# E-bookReaderSch.net
KiCad netlist of a schematic drawn in EAGLE
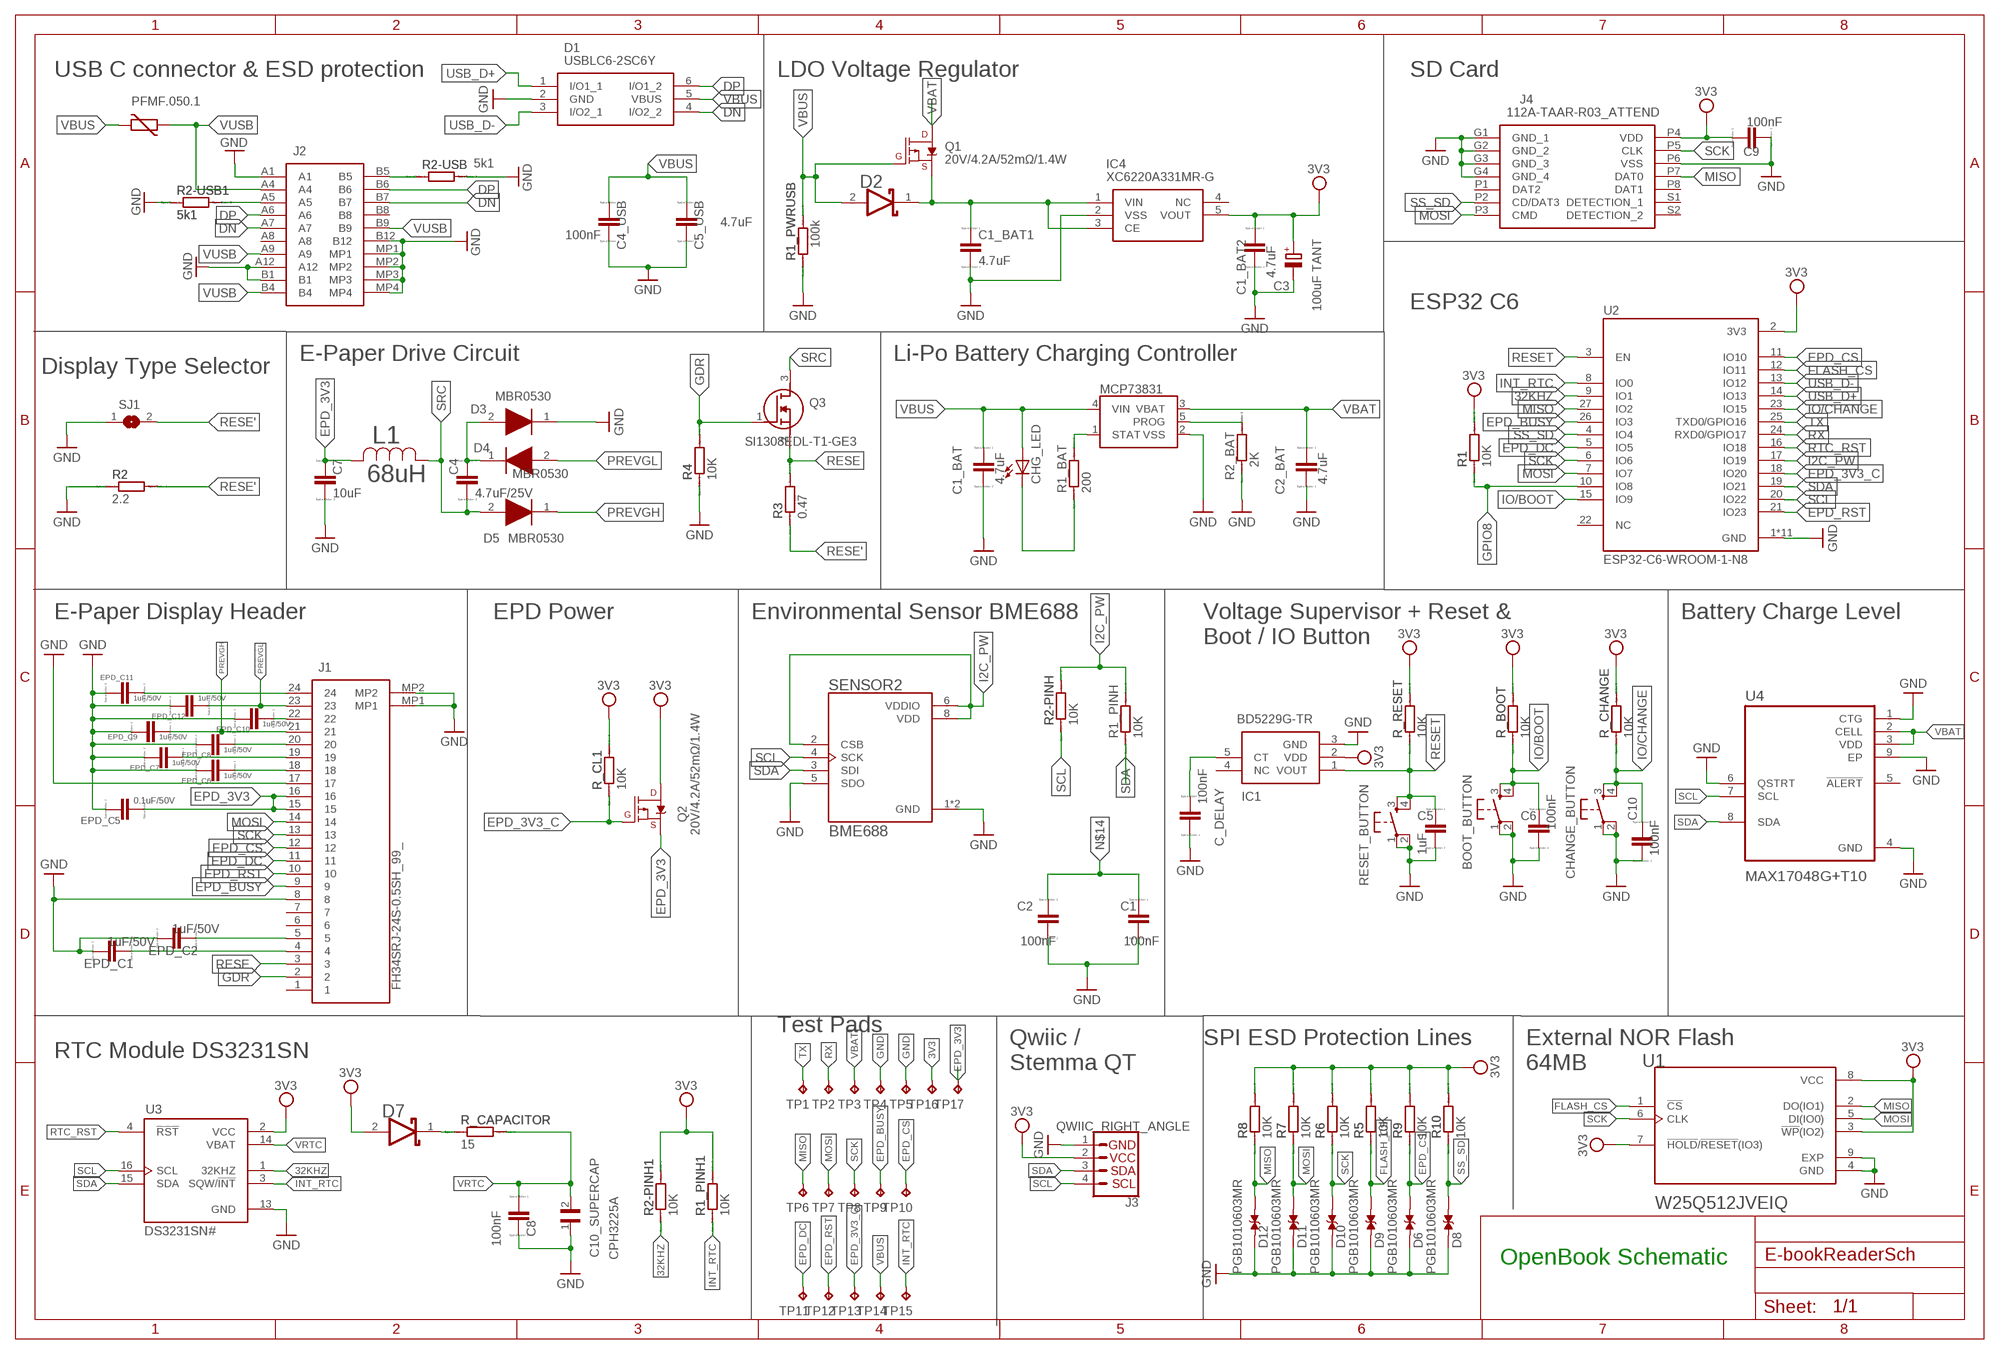
[diagram p0: schematic, sheet 1]

(export (version "E")
  (design (tool "Eeschema 10.0.6"))
  (components
    (comp (ref "BOOT_BUTTON")
      (value "BOOT_BUTTON")
      (footprint "eagle-import:MYBUTTON")
      (libsource (lib "eagle-import") (part "BUTTON_CUSYOMV1"))
    )
    (comp (ref "C1")
      (value "100nF")
      (footprint "eagle-import:EAGLE-LTSPICE_C0402")
      (libsource (lib "eagle-import") (part "EAGLE-LTSPICE_CC0402"))
    )
    (comp (ref "C1_BAT")
      (value "4.7uF")
      (footprint "eagle-import:EAGLE-LTSPICE_C0402")
      (libsource (lib "eagle-import") (part "EAGLE-LTSPICE_CC0402"))
    )
    (comp (ref "C1_BAT1")
      (value "4.7uF")
      (footprint "eagle-import:EAGLE-LTSPICE_C0402")
      (libsource (lib "eagle-import") (part "EAGLE-LTSPICE_CC0402"))
    )
    (comp (ref "C1_BAT2")
      (value "4.7uF")
      (footprint "eagle-import:EAGLE-LTSPICE_C0402")
      (libsource (lib "eagle-import") (part "EAGLE-LTSPICE_CC0402"))
    )
    (comp (ref "C2")
      (value "100nF")
      (footprint "eagle-import:EAGLE-LTSPICE_C0402")
      (libsource (lib "eagle-import") (part "EAGLE-LTSPICE_CC0402"))
    )
    (comp (ref "C2_BAT")
      (value "4.7uF")
      (footprint "eagle-import:EAGLE-LTSPICE_C0402")
      (libsource (lib "eagle-import") (part "EAGLE-LTSPICE_CC0402"))
    )
    (comp (ref "C3")
      (value "100uF TANT")
      (footprint "eagle-import:RCL_CT3528")
      (libsource (lib "eagle-import") (part "RCL_CPOL-EUCT3528"))
    )
    (comp (ref "C4")
      (value "4.7uF/25V")
      (footprint "eagle-import:ESP32_WROVER_EAGLE-LTSPICE_C0402")
      (libsource (lib "eagle-import") (part "ESP32_WROVER_EAGLE-LTSPICE_CC0402"))
    )
    (comp (ref "C4_USB")
      (value "100nF")
      (footprint "eagle-import:ESP32_WROVER_EAGLE-LTSPICE_C0402")
      (libsource (lib "eagle-import") (part "ESP32_WROVER_EAGLE-LTSPICE_CC0402"))
    )
    (comp (ref "C5")
      (value "1uF")
      (footprint "eagle-import:EAGLE-LTSPICE_C0402")
      (libsource (lib "eagle-import") (part "EAGLE-LTSPICE_CC0402"))
    )
    (comp (ref "C5_USB")
      (value "4.7uF")
      (footprint "eagle-import:EAGLE-LTSPICE_C0402")
      (libsource (lib "eagle-import") (part "EAGLE-LTSPICE_CC0402"))
    )
    (comp (ref "C6")
      (value "100nF")
      (footprint "eagle-import:EAGLE-LTSPICE_C0402")
      (libsource (lib "eagle-import") (part "EAGLE-LTSPICE_CC0402"))
    )
    (comp (ref "C7")
      (value "10uF")
      (footprint "eagle-import:ESP32_WROVER_EAGLE-LTSPICE_C0402")
      (libsource (lib "eagle-import") (part "ESP32_WROVER_EAGLE-LTSPICE_CC0402"))
    )
    (comp (ref "C8")
      (value "100nF")
      (footprint "eagle-import:ESP32_WROVER_EAGLE-LTSPICE_C0402")
      (libsource (lib "eagle-import") (part "ESP32_WROVER_EAGLE-LTSPICE_CC0402"))
    )
    (comp (ref "C9")
      (value "100nF")
      (footprint "eagle-import:EAGLE-LTSPICE_C0402")
      (libsource (lib "eagle-import") (part "EAGLE-LTSPICE_CC0402"))
    )
    (comp (ref "C10")
      (value "100nF")
      (footprint "eagle-import:EAGLE-LTSPICE_C0402")
      (libsource (lib "eagle-import") (part "EAGLE-LTSPICE_CC0402"))
    )
    (comp (ref "C10_SUPERCAP")
      (value "CPH3225A")
      (footprint "eagle-import:CAPCP3225X100N")
      (fields (field (name "MF") "Seiko Instruments"))
      (libsource (lib "eagle-import") (part "CPH3225A"))
    )
    (comp (ref "CHANGE_BUTTON")
      (value "CHANGE_BUTTON")
      (footprint "eagle-import:MYBUTTON")
      (libsource (lib "eagle-import") (part "BUTTON_CUSYOMV1"))
    )
    (comp (ref "CHG_LED")
      (value "ADAFRUIT_LEDCHIP-LED0603")
      (footprint "eagle-import:ADAFRUIT_CHIP-LED0603")
      (libsource (lib "eagle-import") (part "ADAFRUIT_LEDCHIP-LED0603"))
    )
    (comp (ref "C_DELAY")
      (value "100nF")
      (footprint "eagle-import:EAGLE-LTSPICE_C0402")
      (libsource (lib "eagle-import") (part "EAGLE-LTSPICE_CC0402"))
    )
    (comp (ref "D1")
      (value "USBLC6-2SC6Y")
      (footprint "eagle-import:SOT95P280X145-6N")
      (fields (field (name "MF") "STMicroelectronics"))
      (libsource (lib "eagle-import") (part "USBLC6-2SC6Y"))
    )
    (comp (ref "D2")
      (value "ESP32_WROVER_AVX---SD0805S020S1R0_AVX_SD0805S020S1R0_0_0AVX_SD0805S020S1R0_0_0")
      (footprint "eagle-import:ESP32_WROVER_AVX---SD0805S020S1R0_AVX_SD0805S020S1R0_0")
      (fields
        (field (name "DIGIKEY_PART_NUMBER") "478-7800-1-ND")
        (field (name "MF") "AVX")
        (field (name "MOUSER_PART_NUMBER") "581-SD0805S020S1R0")
      )
      (libsource (lib "eagle-import") (part "ESP32_WROVER_AVX---SD0805S020S1R0_AVX_SD0805S020S1R0_0_0AVX_SD0805S020S1R0_0_0"))
    )
    (comp (ref "D3")
      (value "MBR0530")
      (footprint "eagle-import:SOD3716X135N")
      (fields (field (name "MF") "ON Semiconductor"))
      (libsource (lib "eagle-import") (part "MBR0530"))
    )
    (comp (ref "D4")
      (value "MBR0530")
      (footprint "eagle-import:SOD3716X135N")
      (fields (field (name "MF") "ON Semiconductor"))
      (libsource (lib "eagle-import") (part "MBR0530"))
    )
    (comp (ref "D5")
      (value "MBR0530")
      (footprint "eagle-import:SOD3716X135N")
      (fields (field (name "MF") "ON Semiconductor"))
      (libsource (lib "eagle-import") (part "MBR0530"))
    )
    (comp (ref "D6")
      (value "PGB1010603MR")
      (footprint "eagle-import:DIOC1608X36N")
      (fields (field (name "MF") "Littelfuse Inc."))
      (libsource (lib "eagle-import") (part "PGB1010603MR"))
    )
    (comp (ref "D7")
      (value "SD0805S020S1R0")
      (footprint "eagle-import:ESP32_WROVER_AVX---SD0805S020S1R0_AVX_SD0805S020S1R0_0")
      (fields
        (field (name "DIGIKEY_PART_NUMBER") "478-7800-1-ND")
        (field (name "MF") "AVX")
        (field (name "MOUSER_PART_NUMBER") "581-SD0805S020S1R0")
      )
      (libsource (lib "eagle-import") (part "ESP32_WROVER_AVX---SD0805S020S1R0_AVX_SD0805S020S1R0_0_0AVX_SD0805S020S1R0_0_0"))
    )
    (comp (ref "D8")
      (value "PGB1010603MR")
      (footprint "eagle-import:DIOC1608X36N")
      (fields (field (name "MF") "Littelfuse Inc."))
      (libsource (lib "eagle-import") (part "PGB1010603MR"))
    )
    (comp (ref "D9")
      (value "PGB1010603MR")
      (footprint "eagle-import:DIOC1608X36N")
      (fields (field (name "MF") "Littelfuse Inc."))
      (libsource (lib "eagle-import") (part "PGB1010603MR"))
    )
    (comp (ref "D10")
      (value "PGB1010603MR")
      (footprint "eagle-import:DIOC1608X36N")
      (fields (field (name "MF") "Littelfuse Inc."))
      (libsource (lib "eagle-import") (part "PGB1010603MR"))
    )
    (comp (ref "D11")
      (value "PGB1010603MR")
      (footprint "eagle-import:DIOC1608X36N")
      (fields (field (name "MF") "Littelfuse Inc."))
      (libsource (lib "eagle-import") (part "PGB1010603MR"))
    )
    (comp (ref "D12")
      (value "PGB1010603MR")
      (footprint "eagle-import:DIOC1608X36N")
      (fields (field (name "MF") "Littelfuse Inc."))
      (libsource (lib "eagle-import") (part "PGB1010603MR"))
    )
    (comp (ref "EPD_C1")
      (value "1uF/50V")
      (footprint "eagle-import:ESP32_WROVER_EAGLE-LTSPICE_C0402")
      (libsource (lib "eagle-import") (part "ESP32_WROVER_EAGLE-LTSPICE_CC0402"))
    )
    (comp (ref "EPD_C2")
      (value "1uF/50V")
      (footprint "eagle-import:ESP32_WROVER_EAGLE-LTSPICE_C0402")
      (libsource (lib "eagle-import") (part "ESP32_WROVER_EAGLE-LTSPICE_CC0402"))
    )
    (comp (ref "EPD_C5")
      (value "0.1uF/50V")
      (footprint "eagle-import:ESP32_WROVER_EAGLE-LTSPICE_C0402")
      (libsource (lib "eagle-import") (part "ESP32_WROVER_EAGLE-LTSPICE_CC0402"))
    )
    (comp (ref "EPD_C6")
      (value "1uF/50V")
      (footprint "eagle-import:ESP32_WROVER_EAGLE-LTSPICE_C0402")
      (libsource (lib "eagle-import") (part "ESP32_WROVER_EAGLE-LTSPICE_CC0402"))
    )
    (comp (ref "EPD_C7")
      (value "1uF/50V")
      (footprint "eagle-import:ESP32_WROVER_EAGLE-LTSPICE_C0402")
      (libsource (lib "eagle-import") (part "ESP32_WROVER_EAGLE-LTSPICE_CC0402"))
    )
    (comp (ref "EPD_C8")
      (value "1uF/50V")
      (footprint "eagle-import:ESP32_WROVER_EAGLE-LTSPICE_C0402")
      (libsource (lib "eagle-import") (part "ESP32_WROVER_EAGLE-LTSPICE_CC0402"))
    )
    (comp (ref "EPD_C9")
      (value "1uF/50V")
      (footprint "eagle-import:ESP32_WROVER_EAGLE-LTSPICE_C0402")
      (libsource (lib "eagle-import") (part "ESP32_WROVER_EAGLE-LTSPICE_CC0402"))
    )
    (comp (ref "EPD_C10")
      (value "1uF/50V")
      (footprint "eagle-import:ESP32_WROVER_EAGLE-LTSPICE_C0402")
      (libsource (lib "eagle-import") (part "ESP32_WROVER_EAGLE-LTSPICE_CC0402"))
    )
    (comp (ref "EPD_C11")
      (value "1uF/50V")
      (footprint "eagle-import:ESP32_WROVER_EAGLE-LTSPICE_C0402")
      (libsource (lib "eagle-import") (part "ESP32_WROVER_EAGLE-LTSPICE_CC0402"))
    )
    (comp (ref "EPD_C12")
      (value "1uF/50V")
      (footprint "eagle-import:ESP32_WROVER_EAGLE-LTSPICE_C0402")
      (libsource (lib "eagle-import") (part "ESP32_WROVER_EAGLE-LTSPICE_CC0402"))
    )
    (comp (ref "IC1")
      (value "BD5229G-TR")
      (footprint "eagle-import:SOT95P280X125-5N")
      (fields (field (name "MOUSER_PART_NUMBER") "755-BD5229G-TR"))
      (libsource (lib "eagle-import") (part "BD5229G-TR"))
    )
    (comp (ref "IC4")
      (value "XC6220A331MR-G")
      (footprint "eagle-import:SOT95P280X120-5N")
      (fields (field (name "MOUSER_PART_NUMBER") "865-XC6220A331MR-G"))
      (libsource (lib "eagle-import") (part "XC6220A331MR-G"))
    )
    (comp (ref "J1")
      (value "FH34SRJ-24S-0.5SH_99_")
      (footprint "eagle-import:FH34SRJ24S05SH99")
      (fields
        (field (name "MANUFACTURER_PART_NUMBER") "FH34SRJ-24S-0.5SH(99)")
        (field (name "MOUSER_PART_NUMBER") "798-FH34SRJ24S05SH99")
      )
      (libsource (lib "eagle-import") (part "FH34SRJ-24S-0.5SH_99_"))
    )
    (comp (ref "J2")
      (value "SAMACSYS_PARTS_USB4110-GF-A")
      (footprint "eagle-import:SAMACSYS_PARTS_USB4110GFA")
      (fields
        (field (name "MANUFACTURER_PART_NUMBER") "USB4110-GF-A")
        (field (name "MOUSER_PART_NUMBER") "640-USB4110-GF-A")
      )
      (libsource (lib "eagle-import") (part "SAMACSYS_PARTS_USB4110-GF-A"))
    )
    (comp (ref "J3")
      (value "QWIIC_RIGHT_ANGLE")
      (footprint "eagle-import:JST04_1MM_RA")
      (libsource (lib "eagle-import") (part "QWIIC_CONNECTORJS-1MM"))
    )
    (comp (ref "J4")
      (value "112A-TAAR-R03_ATTEND")
      (footprint "eagle-import:112ATAARR03ATTEND")
      (fields (field (name "MANUFACTURER_PART_NUMBER") "112A-TAAR-R03 ATTEND"))
      (libsource (lib "eagle-import") (part "112A-TAAR-R03_ATTEND"))
    )
    (comp (ref "L1")
      (value "68uH")
      (footprint "eagle-import:IND_4828-WE-TPC_WRE")
      (fields
        (field (name "MANUFACTURER_PART_NUMBER") "744043680")
        (field (name "COPYRIGHT") "Copyright (C) 2024 Ultra Librarian. All rights reserved.")
      )
      (libsource (lib "eagle-import") (part "744043680IND_4828-WE-TPC_WRE"))
    )
    (comp (ref "MCP73831")
      (value "ESP32_WROVER_SPARKFUN-IC-POWER_MCP73831")
      (footprint "eagle-import:ESP32_WROVER_SPARKFUN-IC-POWER_SOT23-5")
      (libsource (lib "eagle-import") (part "ESP32_WROVER_SPARKFUN-IC-POWER_MCP73831"))
    )
    (comp (ref "PFMF.050.1")
      (value "ESP32C6_VARISTORCN1812")
      (footprint "eagle-import:ESP32C6_VARISTOR_CT_CN1812")
      (libsource (lib "eagle-import") (part "ESP32C6_VARISTORCN1812"))
    )
    (comp (ref "Q1")
      (value "20V/4.2A/52mΩ/1.4W")
      (footprint "eagle-import:ESP32_WROVER_SPARKFUN-DISCRETESEMI_SOT23-3")
      (libsource (lib "eagle-import") (part "ESP32_WROVER_SPARKFUN-DISCRETESEMI_MOSFET_PCH-DMG2305UX-7"))
    )
    (comp (ref "Q2")
      (value "20V/4.2A/52mΩ/1.4W")
      (footprint "eagle-import:ESP32_WROVER_SPARKFUN-DISCRETESEMI_SOT23-3")
      (libsource (lib "eagle-import") (part "ESP32_WROVER_SPARKFUN-DISCRETESEMI_MOSFET_PCH-DMG2305UX-7"))
    )
    (comp (ref "Q3")
      (value "SI1308EDL-T1-GE3")
      (footprint "eagle-import:SOT65P210X110-3N")
      (fields (field (name "MF") "Vishay Siliconix"))
      (libsource (lib "eagle-import") (part "SI1308EDL-T1-GE3"))
    )
    (comp (ref "R1")
      (value "10K")
      (footprint "eagle-import:ESP32_WROVER_EAGLE-LTSPICE_R0402")
      (libsource (lib "eagle-import") (part "ESP32_WROVER_EAGLE-LTSPICE_RR0402"))
    )
    (comp (ref "R1_BAT")
      (value "200")
      (footprint "eagle-import:ESP32_WROVER_EAGLE-LTSPICE_R0402")
      (libsource (lib "eagle-import") (part "ESP32_WROVER_EAGLE-LTSPICE_RR0402"))
    )
    (comp (ref "R1_PINH")
      (value "10K")
      (footprint "eagle-import:ESP32_WROVER_EAGLE-LTSPICE_R0402")
      (libsource (lib "eagle-import") (part "ESP32_WROVER_EAGLE-LTSPICE_RR0402"))
    )
    (comp (ref "R1_PINH1")
      (value "10K")
      (footprint "eagle-import:ESP32_WROVER_EAGLE-LTSPICE_R0402")
      (libsource (lib "eagle-import") (part "ESP32_WROVER_EAGLE-LTSPICE_RR0402"))
    )
    (comp (ref "R1_PWRUSB")
      (value "100k")
      (footprint "eagle-import:ESP32_WROVER_EAGLE-LTSPICE_R0402")
      (libsource (lib "eagle-import") (part "ESP32_WROVER_EAGLE-LTSPICE_RR0402"))
    )
    (comp (ref "R2")
      (value "2.2")
      (footprint "eagle-import:ESP32_WROVER_EAGLE-LTSPICE_R0402")
      (libsource (lib "eagle-import") (part "ESP32_WROVER_EAGLE-LTSPICE_RR0402"))
    )
    (comp (ref "R2-PINH")
      (value "10K")
      (footprint "eagle-import:ESP32_WROVER_EAGLE-LTSPICE_R0402")
      (libsource (lib "eagle-import") (part "ESP32_WROVER_EAGLE-LTSPICE_RR0402"))
    )
    (comp (ref "R2-PINH1")
      (value "10K")
      (footprint "eagle-import:ESP32_WROVER_EAGLE-LTSPICE_R0402")
      (libsource (lib "eagle-import") (part "ESP32_WROVER_EAGLE-LTSPICE_RR0402"))
    )
    (comp (ref "R2-USB")
      (value "5k1")
      (footprint "eagle-import:ESP32_WROVER_EAGLE-LTSPICE_R0402")
      (libsource (lib "eagle-import") (part "ESP32_WROVER_EAGLE-LTSPICE_RR0402"))
    )
    (comp (ref "R2-USB1")
      (value "5k1")
      (footprint "eagle-import:ESP32_WROVER_EAGLE-LTSPICE_R0402")
      (libsource (lib "eagle-import") (part "ESP32_WROVER_EAGLE-LTSPICE_RR0402"))
    )
    (comp (ref "R2_BAT")
      (value "2K")
      (footprint "eagle-import:ESP32_WROVER_EAGLE-LTSPICE_R0402")
      (libsource (lib "eagle-import") (part "ESP32_WROVER_EAGLE-LTSPICE_RR0402"))
    )
    (comp (ref "R3")
      (value "0.47")
      (footprint "eagle-import:ESP32_WROVER_EAGLE-LTSPICE_R0402")
      (libsource (lib "eagle-import") (part "ESP32_WROVER_EAGLE-LTSPICE_RR0402"))
    )
    (comp (ref "R4")
      (value "10K")
      (footprint "eagle-import:ESP32_WROVER_EAGLE-LTSPICE_R0402")
      (libsource (lib "eagle-import") (part "ESP32_WROVER_EAGLE-LTSPICE_RR0402"))
    )
    (comp (ref "R5")
      (value "10K")
      (footprint "eagle-import:ESP32_WROVER_EAGLE-LTSPICE_R0402")
      (libsource (lib "eagle-import") (part "ESP32_WROVER_EAGLE-LTSPICE_RR0402"))
    )
    (comp (ref "R6")
      (value "10K")
      (footprint "eagle-import:ESP32_WROVER_EAGLE-LTSPICE_R0402")
      (libsource (lib "eagle-import") (part "ESP32_WROVER_EAGLE-LTSPICE_RR0402"))
    )
    (comp (ref "R7")
      (value "10K")
      (footprint "eagle-import:ESP32_WROVER_EAGLE-LTSPICE_R0402")
      (libsource (lib "eagle-import") (part "ESP32_WROVER_EAGLE-LTSPICE_RR0402"))
    )
    (comp (ref "R8")
      (value "10K")
      (footprint "eagle-import:ESP32_WROVER_EAGLE-LTSPICE_R0402")
      (libsource (lib "eagle-import") (part "ESP32_WROVER_EAGLE-LTSPICE_RR0402"))
    )
    (comp (ref "R9")
      (value "10K")
      (footprint "eagle-import:ESP32_WROVER_EAGLE-LTSPICE_R0402")
      (libsource (lib "eagle-import") (part "ESP32_WROVER_EAGLE-LTSPICE_RR0402"))
    )
    (comp (ref "R10")
      (value "10K")
      (footprint "eagle-import:ESP32_WROVER_EAGLE-LTSPICE_R0402")
      (libsource (lib "eagle-import") (part "ESP32_WROVER_EAGLE-LTSPICE_RR0402"))
    )
    (comp (ref "RESET_BUTTON")
      (value "RESET_BUTTON")
      (footprint "eagle-import:MYBUTTON")
      (libsource (lib "eagle-import") (part "BUTTON_CUSYOMV1"))
    )
    (comp (ref "R_BOOT")
      (value "10K")
      (footprint "eagle-import:ESP32_WROVER_EAGLE-LTSPICE_R0402")
      (libsource (lib "eagle-import") (part "ESP32_WROVER_EAGLE-LTSPICE_RR0402"))
    )
    (comp (ref "R_CAPACITOR")
      (value "15")
      (footprint "eagle-import:ESP32_WROVER_EAGLE-LTSPICE_R0402")
      (libsource (lib "eagle-import") (part "ESP32_WROVER_EAGLE-LTSPICE_RR0402"))
    )
    (comp (ref "R_CHANGE")
      (value "10K")
      (footprint "eagle-import:ESP32_WROVER_EAGLE-LTSPICE_R0402")
      (libsource (lib "eagle-import") (part "ESP32_WROVER_EAGLE-LTSPICE_RR0402"))
    )
    (comp (ref "R_CL1")
      (value "10K")
      (footprint "eagle-import:ESP32_WROVER_EAGLE-LTSPICE_R0402")
      (libsource (lib "eagle-import") (part "ESP32_WROVER_EAGLE-LTSPICE_RR0402"))
    )
    (comp (ref "R_RESET")
      (value "10K")
      (footprint "eagle-import:ESP32_WROVER_EAGLE-LTSPICE_R0402")
      (libsource (lib "eagle-import") (part "ESP32_WROVER_EAGLE-LTSPICE_RR0402"))
    )
    (comp (ref "SENSOR2")
      (value "BME688")
      (footprint "eagle-import:ESP32_WROVER_BME680_PSON80P300X300X100-8N")
      (fields (field (name "MF") "Bosch Sensortec") (field (name "MP") "BME680"))
      (libsource (lib "eagle-import") (part "ESP32_WROVER_BME680_BME680"))
    )
    (comp (ref "SJ1") (value "SJ") (footprint "eagle-import:SJ") (libsource (lib "eagle-import") (part "SJ")))
    (comp (ref "TP1")
      (value "TPTP20R")
      (footprint "eagle-import:TP20R")
      (libsource (lib "eagle-import") (part "TPTP20R"))
    )
    (comp (ref "TP2")
      (value "TPTP20R")
      (footprint "eagle-import:TP20R")
      (libsource (lib "eagle-import") (part "TPTP20R"))
    )
    (comp (ref "TP3")
      (value "TPTP20R")
      (footprint "eagle-import:TP20R")
      (libsource (lib "eagle-import") (part "TPTP20R"))
    )
    (comp (ref "TP4")
      (value "TPTP20R")
      (footprint "eagle-import:TP20R")
      (libsource (lib "eagle-import") (part "TPTP20R"))
    )
    (comp (ref "TP5")
      (value "TPTP20R")
      (footprint "eagle-import:TP20R")
      (libsource (lib "eagle-import") (part "TPTP20R"))
    )
    (comp (ref "TP6")
      (value "TPTP20R")
      (footprint "eagle-import:TP20R")
      (libsource (lib "eagle-import") (part "TPTP20R"))
    )
    (comp (ref "TP7")
      (value "TPTP20R")
      (footprint "eagle-import:TP20R")
      (libsource (lib "eagle-import") (part "TPTP20R"))
    )
    (comp (ref "TP8")
      (value "TPTP20R")
      (footprint "eagle-import:TP20R")
      (libsource (lib "eagle-import") (part "TPTP20R"))
    )
    (comp (ref "TP9")
      (value "TPTP20R")
      (footprint "eagle-import:TP20R")
      (libsource (lib "eagle-import") (part "TPTP20R"))
    )
    (comp (ref "TP10")
      (value "TPTP20R")
      (footprint "eagle-import:TP20R")
      (libsource (lib "eagle-import") (part "TPTP20R"))
    )
    (comp (ref "TP11")
      (value "TPTP20R")
      (footprint "eagle-import:TP20R")
      (libsource (lib "eagle-import") (part "TPTP20R"))
    )
    (comp (ref "TP12")
      (value "TPTP20R")
      (footprint "eagle-import:TP20R")
      (libsource (lib "eagle-import") (part "TPTP20R"))
    )
    (comp (ref "TP13")
      (value "TPTP20R")
      (footprint "eagle-import:TP20R")
      (libsource (lib "eagle-import") (part "TPTP20R"))
    )
    (comp (ref "TP14")
      (value "TPTP20R")
      (footprint "eagle-import:TP20R")
      (libsource (lib "eagle-import") (part "TPTP20R"))
    )
    (comp (ref "TP15")
      (value "TPTP20R")
      (footprint "eagle-import:TP20R")
      (libsource (lib "eagle-import") (part "TPTP20R"))
    )
    (comp (ref "TP16")
      (value "TPTP20R")
      (footprint "eagle-import:TP20R")
      (libsource (lib "eagle-import") (part "TPTP20R"))
    )
    (comp (ref "TP17")
      (value "TPTP20R")
      (footprint "eagle-import:TP20R")
      (libsource (lib "eagle-import") (part "TPTP20R"))
    )
    (comp (ref "U1")
      (value "W25Q512JVEIQ")
      (footprint "eagle-import:SON127P600X800X80-9N")
      (fields (field (name "MF") "Winbond Electronics"))
      (libsource (lib "eagle-import") (part "W25Q512JVEIQ"))
    )
    (comp (ref "U2")
      (value "ESP32-C6-WROOM-1-N8")
      (footprint "eagle-import:XCVR_ESP32-C6-WROOM-1-N8")
      (fields (field (name "MF") "Espressif Systems"))
      (libsource (lib "eagle-import") (part "ESP32-C6-WROOM-1-N8"))
    )
    (comp (ref "U3")
      (value "DS3231SN#")
      (footprint "eagle-import:SOIC127P1032X265-16N")
      (fields (field (name "MF") "Analog Devices"))
      (libsource (lib "eagle-import") (part "DS3231SN#"))
    )
    (comp (ref "U4")
      (value "MAX17048G+T10")
      (footprint "eagle-import:SON50P200X200X80-9N")
      (fields (field (name "MF") "Analog Devices"))
      (libsource (lib "eagle-import") (part "MAX17048G+T10"))
    )
  )
  (nets
    (net (code "1") (name "3V3") (class "Default")
      (node (ref "C1_BAT2") (pin "1") (pinfunction "1_1") (pintype "passive"))
      (node (ref "C3") (pin "+") (pinfunction "+_+") (pintype "passive"))
      (node (ref "C9") (pin "1") (pinfunction "1_1") (pintype "passive"))
      (node (ref "D7") (pin "2") (pinfunction "ANODE_2") (pintype "bidirectional"))
      (node (ref "IC1") (pin "2") (pinfunction "VDD_2") (pintype "bidirectional"))
      (node (ref "IC4") (pin "5") (pinfunction "VOUT_5") (pintype "bidirectional"))
      (node (ref "J3") (pin "2") (pinfunction "2_2") (pintype "power_in"))
      (node (ref "J4") (pin "P4") (pinfunction "VDD_P4") (pintype "bidirectional"))
      (node (ref "Q2") (pin "3") (pinfunction "D_3") (pintype "bidirectional"))
      (node (ref "R1") (pin "2") (pinfunction "2_2") (pintype "passive"))
      (node (ref "R10") (pin "2") (pinfunction "2_2") (pintype "passive"))
      (node (ref "R1_PINH1") (pin "2") (pinfunction "2_2") (pintype "passive"))
      (node (ref "R2-PINH1") (pin "2") (pinfunction "2_2") (pintype "passive"))
      (node (ref "R5") (pin "2") (pinfunction "2_2") (pintype "passive"))
      (node (ref "R6") (pin "2") (pinfunction "2_2") (pintype "passive"))
      (node (ref "R7") (pin "2") (pinfunction "2_2") (pintype "passive"))
      (node (ref "R8") (pin "2") (pinfunction "2_2") (pintype "passive"))
      (node (ref "R9") (pin "2") (pinfunction "2_2") (pintype "passive"))
      (node (ref "R_BOOT") (pin "2") (pinfunction "2_2") (pintype "passive"))
      (node (ref "R_CHANGE") (pin "2") (pinfunction "2_2") (pintype "passive"))
      (node (ref "R_CL1") (pin "2") (pinfunction "2_2") (pintype "passive"))
      (node (ref "R_RESET") (pin "2") (pinfunction "2_2") (pintype "passive"))
      (node (ref "TP16") (pin "TP") (pinfunction "TP_TP") (pintype "input"))
      (node (ref "U1") (pin "3") (pinfunction "~{WP}(IO2)_3") (pintype "bidirectional"))
      (node (ref "U1") (pin "7") (pinfunction "~{HOLD}/~{RESET}(IO3)_7") (pintype "bidirectional"))
      (node (ref "U1") (pin "8") (pinfunction "VCC_8") (pintype "power_in"))
      (node (ref "U2") (pin "2") (pinfunction "3V3_2") (pintype "power_in"))
      (node (ref "U3") (pin "2") (pinfunction "VCC_2") (pintype "power_in"))
    )
    (net (code "2") (name "32KHZ") (class "Default")
      (node (ref "R2-PINH1") (pin "1") (pinfunction "1_1") (pintype "passive"))
      (node (ref "U2") (pin "9") (pinfunction "IO1_9") (pintype "bidirectional"))
      (node (ref "U3") (pin "1") (pinfunction "32KHZ_1") (pintype "output"))
    )
    (net (code "3") (name "DN") (class "Default")
      (node (ref "D1") (pin "4") (pinfunction "I/O2_2_4") (pintype "bidirectional"))
      (node (ref "J2") (pin "A7") (pinfunction "A7_A7") (pintype "bidirectional"))
      (node (ref "J2") (pin "B7") (pinfunction "B7_B7") (pintype "bidirectional"))
    )
    (net (code "4") (name "DP") (class "Default")
      (node (ref "D1") (pin "6") (pinfunction "I/O1_2_6") (pintype "bidirectional"))
      (node (ref "J2") (pin "A6") (pinfunction "A6_A6") (pintype "bidirectional"))
      (node (ref "J2") (pin "B6") (pinfunction "B6_B6") (pintype "bidirectional"))
    )
    (net (code "5") (name "EPD_3V3") (class "Default")
      (node (ref "C7") (pin "1") (pinfunction "1_1") (pintype "passive"))
      (node (ref "EPD_C5") (pin "1") (pinfunction "1_1") (pintype "passive"))
      (node (ref "J1") (pin "15") (pinfunction "15_15") (pintype "bidirectional"))
      (node (ref "J1") (pin "16") (pinfunction "16_16") (pintype "bidirectional"))
      (node (ref "L1") (pin "2") (pinfunction "2_2") (pintype "passive"))
      (node (ref "Q2") (pin "2") (pinfunction "S_2") (pintype "bidirectional"))
      (node (ref "TP17") (pin "TP") (pinfunction "TP_TP") (pintype "input"))
    )
    (net (code "6") (name "EPD_3V3_C") (class "Default")
      (node (ref "Q2") (pin "1") (pinfunction "G_1") (pintype "bidirectional"))
      (node (ref "R_CL1") (pin "1") (pinfunction "1_1") (pintype "passive"))
      (node (ref "TP13") (pin "TP") (pinfunction "TP_TP") (pintype "input"))
      (node (ref "U2") (pin "18") (pinfunction "IO20_18") (pintype "bidirectional"))
    )
    (net (code "7") (name "EPD_BUSY") (class "Default")
      (node (ref "J1") (pin "9") (pinfunction "9_9") (pintype "bidirectional"))
      (node (ref "TP9") (pin "TP") (pinfunction "TP_TP") (pintype "input"))
      (node (ref "U2") (pin "26") (pinfunction "IO3_26") (pintype "bidirectional"))
    )
    (net (code "8") (name "EPD_CS") (class "Default")
      (node (ref "D6") (pin "2") (pinfunction "2_2") (pintype "passive"))
      (node (ref "J1") (pin "12") (pinfunction "12_12") (pintype "bidirectional"))
      (node (ref "R9") (pin "1") (pinfunction "1_1") (pintype "passive"))
      (node (ref "TP10") (pin "TP") (pinfunction "TP_TP") (pintype "input"))
      (node (ref "U2") (pin "11") (pinfunction "IO10_11") (pintype "bidirectional"))
    )
    (net (code "9") (name "EPD_DC") (class "Default")
      (node (ref "J1") (pin "11") (pinfunction "11_11") (pintype "bidirectional"))
      (node (ref "TP11") (pin "TP") (pinfunction "TP_TP") (pintype "input"))
      (node (ref "U2") (pin "5") (pinfunction "IO5_5") (pintype "bidirectional"))
    )
    (net (code "10") (name "EPD_RST") (class "Default")
      (node (ref "J1") (pin "10") (pinfunction "10_10") (pintype "bidirectional"))
      (node (ref "TP12") (pin "TP") (pinfunction "TP_TP") (pintype "input"))
      (node (ref "U2") (pin "21") (pinfunction "IO23_21") (pintype "bidirectional"))
    )
    (net (code "11") (name "FLASH_CS") (class "Default")
      (node (ref "D9") (pin "2") (pinfunction "2_2") (pintype "passive"))
      (node (ref "R5") (pin "1") (pinfunction "1_1") (pintype "passive"))
      (node (ref "U1") (pin "1") (pinfunction "~{CS}_1") (pintype "input"))
      (node (ref "U2") (pin "12") (pinfunction "IO11_12") (pintype "bidirectional"))
    )
    (net (code "12") (name "GDR") (class "Default")
      (node (ref "J1") (pin "2") (pinfunction "2_2") (pintype "bidirectional"))
      (node (ref "Q3") (pin "1") (pinfunction "G_1") (pintype "bidirectional"))
      (node (ref "R4") (pin "2") (pinfunction "2_2") (pintype "passive"))
    )
    (net (code "13") (name "GND") (class "Default")
      (node (ref "BOOT_BUTTON") (pin "1") (pinfunction "1_1") (pintype "passive"))
      (node (ref "BOOT_BUTTON") (pin "2") (pinfunction "2_2") (pintype "passive"))
      (node (ref "C1") (pin "2") (pinfunction "2_2") (pintype "passive"))
      (node (ref "C10") (pin "2") (pinfunction "2_2") (pintype "passive"))
      (node (ref "C10_SUPERCAP") (pin "1") (pinfunction "1_1") (pintype "passive"))
      (node (ref "C1_BAT") (pin "2") (pinfunction "2_2") (pintype "passive"))
      (node (ref "C1_BAT1") (pin "2") (pinfunction "2_2") (pintype "passive"))
      (node (ref "C1_BAT2") (pin "2") (pinfunction "2_2") (pintype "passive"))
      (node (ref "C2") (pin "2") (pinfunction "2_2") (pintype "passive"))
      (node (ref "C2_BAT") (pin "2") (pinfunction "2_2") (pintype "passive"))
      (node (ref "C3") (pin "-") (pinfunction "-_-") (pintype "passive"))
      (node (ref "C4_USB") (pin "2") (pinfunction "2_2") (pintype "passive"))
      (node (ref "C5") (pin "2") (pinfunction "2_2") (pintype "passive"))
      (node (ref "C5_USB") (pin "2") (pinfunction "2_2") (pintype "passive"))
      (node (ref "C6") (pin "2") (pinfunction "2_2") (pintype "passive"))
      (node (ref "C7") (pin "2") (pinfunction "2_2") (pintype "passive"))
      (node (ref "C8") (pin "2") (pinfunction "2_2") (pintype "passive"))
      (node (ref "C9") (pin "2") (pinfunction "2_2") (pintype "passive"))
      (node (ref "CHANGE_BUTTON") (pin "1") (pinfunction "1_1") (pintype "passive"))
      (node (ref "CHANGE_BUTTON") (pin "2") (pinfunction "2_2") (pintype "passive"))
      (node (ref "C_DELAY") (pin "2") (pinfunction "2_2") (pintype "passive"))
      (node (ref "D1") (pin "2") (pinfunction "GND_2") (pintype "bidirectional"))
      (node (ref "D10") (pin "1") (pinfunction "1_1") (pintype "passive"))
      (node (ref "D11") (pin "1") (pinfunction "1_1") (pintype "passive"))
      (node (ref "D12") (pin "1") (pinfunction "1_1") (pintype "passive"))
      (node (ref "D3") (pin "1") (pinfunction "K_1") (pintype "bidirectional"))
      (node (ref "D6") (pin "1") (pinfunction "1_1") (pintype "passive"))
      (node (ref "D8") (pin "1") (pinfunction "1_1") (pintype "passive"))
      (node (ref "D9") (pin "1") (pinfunction "1_1") (pintype "passive"))
      (node (ref "EPD_C1") (pin "2") (pinfunction "2_2") (pintype "passive"))
      (node (ref "EPD_C10") (pin "2") (pinfunction "2_2") (pintype "passive"))
      (node (ref "EPD_C11") (pin "2") (pinfunction "2_2") (pintype "passive"))
      (node (ref "EPD_C12") (pin "2") (pinfunction "2_2") (pintype "passive"))
      (node (ref "EPD_C2") (pin "2") (pinfunction "2_2") (pintype "passive"))
      (node (ref "EPD_C5") (pin "2") (pinfunction "2_2") (pintype "passive"))
      (node (ref "EPD_C6") (pin "2") (pinfunction "2_2") (pintype "passive"))
      (node (ref "EPD_C7") (pin "2") (pinfunction "2_2") (pintype "passive"))
      (node (ref "EPD_C8") (pin "2") (pinfunction "2_2") (pintype "passive"))
      (node (ref "EPD_C9") (pin "2") (pinfunction "2_2") (pintype "passive"))
      (node (ref "IC1") (pin "3") (pinfunction "GND_3") (pintype "bidirectional"))
      (node (ref "IC4") (pin "2") (pinfunction "VSS_2") (pintype "bidirectional"))
      (node (ref "J1") (pin "17") (pinfunction "17_17") (pintype "bidirectional"))
      (node (ref "J1") (pin "8") (pinfunction "8_8") (pintype "bidirectional"))
      (node (ref "J1") (pin "MP1") (pinfunction "MP1_MP1") (pintype "bidirectional"))
      (node (ref "J1") (pin "MP2") (pinfunction "MP2_MP2") (pintype "bidirectional"))
      (node (ref "J2") (pin "A1") (pinfunction "A1_A1") (pintype "bidirectional"))
      (node (ref "J2") (pin "A12") (pinfunction "A12_A12") (pintype "bidirectional"))
      (node (ref "J2") (pin "B1") (pinfunction "B1_B1") (pintype "bidirectional"))
      (node (ref "J2") (pin "B12") (pinfunction "B12_B12") (pintype "bidirectional"))
      (node (ref "J2") (pin "MP1") (pinfunction "MP1_MP1") (pintype "bidirectional"))
      (node (ref "J2") (pin "MP2") (pinfunction "MP2_MP2") (pintype "bidirectional"))
      (node (ref "J2") (pin "MP3") (pinfunction "MP3_MP3") (pintype "bidirectional"))
      (node (ref "J2") (pin "MP4") (pinfunction "MP4_MP4") (pintype "bidirectional"))
      (node (ref "J3") (pin "1") (pinfunction "1_1") (pintype "power_in"))
      (node (ref "J4") (pin "G1") (pinfunction "GND_1_G1") (pintype "bidirectional"))
      (node (ref "J4") (pin "G2") (pinfunction "GND_2_G2") (pintype "bidirectional"))
      (node (ref "J4") (pin "G3") (pinfunction "GND_3_G3") (pintype "bidirectional"))
      (node (ref "J4") (pin "G4") (pinfunction "GND_4_G4") (pintype "bidirectional"))
      (node (ref "J4") (pin "P6") (pinfunction "VSS_P6") (pintype "bidirectional"))
      (node (ref "MCP73831") (pin "2") (pinfunction "VSS_2") (pintype "power_in"))
      (node (ref "R1_PWRUSB") (pin "1") (pinfunction "1_1") (pintype "passive"))
      (node (ref "R2") (pin "1") (pinfunction "1_1") (pintype "passive"))
      (node (ref "R2-USB") (pin "2") (pinfunction "2_2") (pintype "passive"))
      (node (ref "R2-USB1") (pin "1") (pinfunction "1_1") (pintype "passive"))
      (node (ref "R2_BAT") (pin "1") (pinfunction "1_1") (pintype "passive"))
      (node (ref "R4") (pin "1") (pinfunction "1_1") (pintype "passive"))
      (node (ref "RESET_BUTTON") (pin "1") (pinfunction "1_1") (pintype "passive"))
      (node (ref "RESET_BUTTON") (pin "2") (pinfunction "2_2") (pintype "passive"))
      (node (ref "SENSOR2") (pin "1") (pinfunction "GND_1") (pintype "power_in"))
      (node (ref "SENSOR2") (pin "5") (pinfunction "SDO_5") (pintype "bidirectional"))
      (node (ref "SENSOR2") (pin "7") (pinfunction "GND_7") (pintype "power_in"))
      (node (ref "SJ1") (pin "1") (pinfunction "1_1") (pintype "passive"))
      (node (ref "TP4") (pin "TP") (pinfunction "TP_TP") (pintype "input"))
      (node (ref "TP5") (pin "TP") (pinfunction "TP_TP") (pintype "input"))
      (node (ref "U1") (pin "4") (pinfunction "GND_4") (pintype "power_in"))
      (node (ref "U1") (pin "9") (pinfunction "EXP_9") (pintype "passive"))
      (node (ref "U2") (pin "1") (pinfunction "GND_1") (pintype "power_in"))
      (node (ref "U2") (pin "28") (pinfunction "GND_28") (pintype "power_in"))
      (node (ref "U2") (pin "29_1") (pinfunction "GND_29_1") (pintype "power_in"))
      (node (ref "U2") (pin "29_2") (pinfunction "GND_29_2") (pintype "power_in"))
      (node (ref "U2") (pin "29_3") (pinfunction "GND_29_3") (pintype "power_in"))
      (node (ref "U2") (pin "29_4") (pinfunction "GND_29_4") (pintype "power_in"))
      (node (ref "U2") (pin "29_5") (pinfunction "GND_29_5") (pintype "power_in"))
      (node (ref "U2") (pin "29_6") (pinfunction "GND_29_6") (pintype "power_in"))
      (node (ref "U2") (pin "29_7") (pinfunction "GND_29_7") (pintype "power_in"))
      (node (ref "U2") (pin "29_8") (pinfunction "GND_29_8") (pintype "power_in"))
      (node (ref "U2") (pin "29_9") (pinfunction "GND_29_9") (pintype "power_in"))
      (node (ref "U3") (pin "13") (pinfunction "GND_13") (pintype "power_in"))
      (node (ref "U4") (pin "1") (pinfunction "CTG_1") (pintype "power_in"))
      (node (ref "U4") (pin "4") (pinfunction "GND_4") (pintype "power_in"))
      (node (ref "U4") (pin "6") (pinfunction "QSTRT_6") (pintype "input"))
      (node (ref "U4") (pin "9") (pinfunction "EP_9") (pintype "power_in"))
    )
    (net (code "14") (name "GPIO8") (class "Default")
      (node (ref "R1") (pin "1") (pinfunction "1_1") (pintype "passive"))
      (node (ref "U2") (pin "10") (pinfunction "IO8_10") (pintype "bidirectional"))
    )
    (net (code "15") (name "I2C_PW") (class "Default")
      (node (ref "R1_PINH") (pin "2") (pinfunction "2_2") (pintype "passive"))
      (node (ref "R2-PINH") (pin "2") (pinfunction "2_2") (pintype "passive"))
      (node (ref "SENSOR2") (pin "2") (pinfunction "CSB_2") (pintype "input"))
      (node (ref "SENSOR2") (pin "6") (pinfunction "VDDIO_6") (pintype "power_in"))
      (node (ref "SENSOR2") (pin "8") (pinfunction "VDD_8") (pintype "power_in"))
      (node (ref "U2") (pin "17") (pinfunction "IO19_17") (pintype "bidirectional"))
    )
    (net (code "16") (name "INT_RTC") (class "Default")
      (node (ref "R1_PINH1") (pin "1") (pinfunction "1_1") (pintype "passive"))
      (node (ref "TP15") (pin "TP") (pinfunction "TP_TP") (pintype "input"))
      (node (ref "U2") (pin "8") (pinfunction "IO0_8") (pintype "bidirectional"))
      (node (ref "U3") (pin "3") (pinfunction "SQW/~{INT}_3") (pintype "output"))
    )
    (net (code "17") (name "IO{slash}BOOT") (class "Default")
      (node (ref "BOOT_BUTTON") (pin "3") (pinfunction "3_3") (pintype "passive"))
      (node (ref "BOOT_BUTTON") (pin "4") (pinfunction "4_4") (pintype "passive"))
      (node (ref "C6") (pin "1") (pinfunction "1_1") (pintype "passive"))
      (node (ref "R_BOOT") (pin "1") (pinfunction "1_1") (pintype "passive"))
      (node (ref "U2") (pin "15") (pinfunction "IO9_15") (pintype "bidirectional"))
    )
    (net (code "18") (name "IO{slash}CHANGE") (class "Default")
      (node (ref "C10") (pin "1") (pinfunction "1_1") (pintype "passive"))
      (node (ref "CHANGE_BUTTON") (pin "3") (pinfunction "3_3") (pintype "passive"))
      (node (ref "CHANGE_BUTTON") (pin "4") (pinfunction "4_4") (pintype "passive"))
      (node (ref "R_CHANGE") (pin "1") (pinfunction "1_1") (pintype "passive"))
      (node (ref "U2") (pin "23") (pinfunction "IO15_23") (pintype "bidirectional"))
    )
    (net (code "19") (name "MISO") (class "Default")
      (node (ref "D12") (pin "2") (pinfunction "2_2") (pintype "passive"))
      (node (ref "J4") (pin "P7") (pinfunction "DAT0_P7") (pintype "bidirectional"))
      (node (ref "R8") (pin "1") (pinfunction "1_1") (pintype "passive"))
      (node (ref "TP6") (pin "TP") (pinfunction "TP_TP") (pintype "input"))
      (node (ref "U1") (pin "2") (pinfunction "DO(IO1)_2") (pintype "bidirectional"))
      (node (ref "U2") (pin "27") (pinfunction "IO2_27") (pintype "bidirectional"))
    )
    (net (code "20") (name "MOSI") (class "Default")
      (node (ref "D11") (pin "2") (pinfunction "2_2") (pintype "passive"))
      (node (ref "J1") (pin "14") (pinfunction "14_14") (pintype "bidirectional"))
      (node (ref "J4") (pin "P3") (pinfunction "CMD_P3") (pintype "bidirectional"))
      (node (ref "R7") (pin "1") (pinfunction "1_1") (pintype "passive"))
      (node (ref "TP7") (pin "TP") (pinfunction "TP_TP") (pintype "input"))
      (node (ref "U1") (pin "5") (pinfunction "DI(IO0)_5") (pintype "bidirectional"))
      (node (ref "U2") (pin "7") (pinfunction "IO7_7") (pintype "bidirectional"))
    )
    (net (code "21") (name "N$14") (class "Default")
      (node (ref "C1") (pin "1") (pinfunction "1_1") (pintype "passive"))
      (node (ref "C2") (pin "1") (pinfunction "1_1") (pintype "passive"))
    )
    (net (code "22") (name "Net-(CHG_LED-PadC)") (class "Default")
      (node (ref "CHG_LED") (pin "C") (pinfunction "C_C") (pintype "passive"))
      (node (ref "R1_BAT") (pin "1") (pinfunction "1_1") (pintype "passive"))
    )
    (net (code "23") (name "Net-(D2-CATHODE)") (class "Default")
      (node (ref "C1_BAT1") (pin "1") (pinfunction "1_1") (pintype "passive"))
      (node (ref "D2") (pin "1") (pinfunction "CATHODE_1") (pintype "bidirectional"))
      (node (ref "IC4") (pin "1") (pinfunction "VIN_1") (pintype "bidirectional"))
      (node (ref "IC4") (pin "3") (pinfunction "CE_3") (pintype "bidirectional"))
      (node (ref "Q1") (pin "2") (pinfunction "S_2") (pintype "bidirectional"))
    )
    (net (code "24") (name "Net-(D3-A)") (class "Default")
      (node (ref "C4") (pin "1") (pinfunction "1_1") (pintype "passive"))
      (node (ref "D3") (pin "2") (pinfunction "A_2") (pintype "bidirectional"))
      (node (ref "D4") (pin "1") (pinfunction "K_1") (pintype "bidirectional"))
    )
    (net (code "25") (name "Net-(D7-CATHODE)") (class "Default")
      (node (ref "D7") (pin "1") (pinfunction "CATHODE_1") (pintype "bidirectional"))
      (node (ref "R_CAPACITOR") (pin "1") (pinfunction "1_1") (pintype "passive"))
    )
    (net (code "26") (name "Net-(EPD_C1-Pad1)") (class "Default")
      (node (ref "EPD_C1") (pin "1") (pinfunction "1_1") (pintype "passive"))
      (node (ref "J1") (pin "4") (pinfunction "4_4") (pintype "bidirectional"))
    )
    (net (code "27") (name "Net-(EPD_C2-Pad1)") (class "Default")
      (node (ref "EPD_C2") (pin "1") (pinfunction "1_1") (pintype "passive"))
      (node (ref "J1") (pin "5") (pinfunction "5_5") (pintype "bidirectional"))
    )
    (net (code "28") (name "Net-(EPD_C6-Pad1)") (class "Default")
      (node (ref "EPD_C6") (pin "1") (pinfunction "1_1") (pintype "passive"))
      (node (ref "J1") (pin "18") (pinfunction "18_18") (pintype "bidirectional"))
    )
    (net (code "29") (name "Net-(EPD_C7-Pad1)") (class "Default")
      (node (ref "EPD_C7") (pin "1") (pinfunction "1_1") (pintype "passive"))
      (node (ref "J1") (pin "19") (pinfunction "19_19") (pintype "bidirectional"))
    )
    (net (code "30") (name "Net-(EPD_C8-Pad1)") (class "Default")
      (node (ref "EPD_C8") (pin "1") (pinfunction "1_1") (pintype "passive"))
      (node (ref "J1") (pin "20") (pinfunction "20_20") (pintype "bidirectional"))
    )
    (net (code "31") (name "Net-(EPD_C10-Pad1)") (class "Default")
      (node (ref "EPD_C10") (pin "1") (pinfunction "1_1") (pintype "passive"))
      (node (ref "J1") (pin "22") (pinfunction "22_22") (pintype "bidirectional"))
    )
    (net (code "32") (name "Net-(EPD_C11-Pad1)") (class "Default")
      (node (ref "EPD_C11") (pin "1") (pinfunction "1_1") (pintype "passive"))
      (node (ref "J1") (pin "24") (pinfunction "24_24") (pintype "bidirectional"))
    )
    (net (code "33") (name "Net-(IC1-CT)") (class "Default")
      (node (ref "C_DELAY") (pin "1") (pinfunction "1_1") (pintype "passive"))
      (node (ref "IC1") (pin "5") (pinfunction "CT_5") (pintype "bidirectional"))
    )
    (net (code "34") (name "Net-(J2-PadA5)") (class "Default")
      (node (ref "J2") (pin "A5") (pinfunction "A5_A5") (pintype "bidirectional"))
      (node (ref "R2-USB1") (pin "2") (pinfunction "2_2") (pintype "passive"))
    )
    (net (code "35") (name "Net-(J2-PadB5)") (class "Default")
      (node (ref "J2") (pin "B5") (pinfunction "B5_B5") (pintype "bidirectional"))
      (node (ref "R2-USB") (pin "1") (pinfunction "1_1") (pintype "passive"))
    )
    (net (code "36") (name "Net-(MCP73831-PROG)") (class "Default")
      (node (ref "MCP73831") (pin "5") (pinfunction "PROG_5") (pintype "input"))
      (node (ref "R2_BAT") (pin "2") (pinfunction "2_2") (pintype "passive"))
    )
    (net (code "37") (name "Net-(MCP73831-STAT)") (class "Default")
      (node (ref "MCP73831") (pin "1") (pinfunction "STAT_1") (pintype "output"))
      (node (ref "R1_BAT") (pin "2") (pinfunction "2_2") (pintype "passive"))
    )
    (net (code "38") (name "PREVGH") (class "Default")
      (node (ref "D5") (pin "1") (pinfunction "K_1") (pintype "bidirectional"))
      (node (ref "EPD_C9") (pin "1") (pinfunction "1_1") (pintype "passive"))
      (node (ref "J1") (pin "21") (pinfunction "21_21") (pintype "bidirectional"))
    )
    (net (code "39") (name "PREVGL") (class "Default")
      (node (ref "D4") (pin "2") (pinfunction "A_2") (pintype "bidirectional"))
      (node (ref "EPD_C12") (pin "1") (pinfunction "1_1") (pintype "passive"))
      (node (ref "J1") (pin "23") (pinfunction "23_23") (pintype "bidirectional"))
    )
    (net (code "40") (name "RESE") (class "Default")
      (node (ref "J1") (pin "3") (pinfunction "3_3") (pintype "bidirectional"))
      (node (ref "Q3") (pin "2") (pinfunction "S_2") (pintype "bidirectional"))
      (node (ref "R3") (pin "2") (pinfunction "2_2") (pintype "passive"))
    )
    (net (code "41") (name "RESE'") (class "Default")
      (node (ref "R2") (pin "2") (pinfunction "2_2") (pintype "passive"))
      (node (ref "R3") (pin "1") (pinfunction "1_1") (pintype "passive"))
      (node (ref "SJ1") (pin "2") (pinfunction "2_2") (pintype "passive"))
    )
    (net (code "42") (name "RESET") (class "Default")
      (node (ref "C5") (pin "1") (pinfunction "1_1") (pintype "passive"))
      (node (ref "IC1") (pin "1") (pinfunction "VOUT_1") (pintype "bidirectional"))
      (node (ref "RESET_BUTTON") (pin "3") (pinfunction "3_3") (pintype "passive"))
      (node (ref "RESET_BUTTON") (pin "4") (pinfunction "4_4") (pintype "passive"))
      (node (ref "R_RESET") (pin "1") (pinfunction "1_1") (pintype "passive"))
      (node (ref "U2") (pin "3") (pinfunction "EN_3") (pintype "input"))
    )
    (net (code "43") (name "RTC_RST") (class "Default")
      (node (ref "U2") (pin "16") (pinfunction "IO18_16") (pintype "bidirectional"))
      (node (ref "U3") (pin "4") (pinfunction "~{RST}_4") (pintype "input"))
    )
    (net (code "44") (name "RX") (class "Default")
      (node (ref "TP2") (pin "TP") (pinfunction "TP_TP") (pintype "input"))
      (node (ref "U2") (pin "24") (pinfunction "RXD0/GPIO17_24") (pintype "bidirectional"))
    )
    (net (code "45") (name "SCK") (class "Default")
      (node (ref "D10") (pin "2") (pinfunction "2_2") (pintype "passive"))
      (node (ref "J1") (pin "13") (pinfunction "13_13") (pintype "bidirectional"))
      (node (ref "J4") (pin "P5") (pinfunction "CLK_P5") (pintype "bidirectional"))
      (node (ref "R6") (pin "1") (pinfunction "1_1") (pintype "passive"))
      (node (ref "TP8") (pin "TP") (pinfunction "TP_TP") (pintype "input"))
      (node (ref "U1") (pin "6") (pinfunction "CLK_6") (pintype "input"))
      (node (ref "U2") (pin "6") (pinfunction "IO6_6") (pintype "bidirectional"))
    )
    (net (code "46") (name "SCL") (class "Default")
      (node (ref "J3") (pin "4") (pinfunction "4_4") (pintype "passive"))
      (node (ref "R2-PINH") (pin "1") (pinfunction "1_1") (pintype "passive"))
      (node (ref "SENSOR2") (pin "4") (pinfunction "SCK_4") (pintype "input"))
      (node (ref "U2") (pin "20") (pinfunction "IO22_20") (pintype "bidirectional"))
      (node (ref "U3") (pin "16") (pinfunction "SCL_16") (pintype "input"))
      (node (ref "U4") (pin "7") (pinfunction "SCL_7") (pintype "input"))
    )
    (net (code "47") (name "SDA") (class "Default")
      (node (ref "J3") (pin "3") (pinfunction "3_3") (pintype "passive"))
      (node (ref "R1_PINH") (pin "1") (pinfunction "1_1") (pintype "passive"))
      (node (ref "SENSOR2") (pin "3") (pinfunction "SDI_3") (pintype "bidirectional"))
      (node (ref "U2") (pin "19") (pinfunction "IO21_19") (pintype "bidirectional"))
      (node (ref "U3") (pin "15") (pinfunction "SDA_15") (pintype "bidirectional"))
      (node (ref "U4") (pin "8") (pinfunction "SDA_8") (pintype "bidirectional"))
    )
    (net (code "48") (name "SRC") (class "Default")
      (node (ref "C4") (pin "2") (pinfunction "2_2") (pintype "passive"))
      (node (ref "D5") (pin "2") (pinfunction "A_2") (pintype "bidirectional"))
      (node (ref "L1") (pin "1") (pinfunction "1_1") (pintype "passive"))
      (node (ref "Q3") (pin "3") (pinfunction "D_3") (pintype "bidirectional"))
    )
    (net (code "49") (name "SS_SD") (class "Default")
      (node (ref "D8") (pin "2") (pinfunction "2_2") (pintype "passive"))
      (node (ref "J4") (pin "P2") (pinfunction "CD/DAT3_P2") (pintype "bidirectional"))
      (node (ref "R10") (pin "1") (pinfunction "1_1") (pintype "passive"))
      (node (ref "U2") (pin "4") (pinfunction "IO4_4") (pintype "bidirectional"))
    )
    (net (code "50") (name "TX") (class "Default")
      (node (ref "TP1") (pin "TP") (pinfunction "TP_TP") (pintype "input"))
      (node (ref "U2") (pin "25") (pinfunction "TXD0/GPIO16_25") (pintype "bidirectional"))
    )
    (net (code "51") (name "USB_D+") (class "Default")
      (node (ref "D1") (pin "1") (pinfunction "I/O1_1_1") (pintype "bidirectional"))
      (node (ref "U2") (pin "14") (pinfunction "IO13_14") (pintype "bidirectional"))
    )
    (net (code "52") (name "USB_D-") (class "Default")
      (node (ref "D1") (pin "3") (pinfunction "I/O2_1_3") (pintype "bidirectional"))
      (node (ref "U2") (pin "13") (pinfunction "IO12_13") (pintype "bidirectional"))
    )
    (net (code "53") (name "VBAT") (class "Default")
      (node (ref "C2_BAT") (pin "1") (pinfunction "1_1") (pintype "passive"))
      (node (ref "MCP73831") (pin "3") (pinfunction "VBAT_3") (pintype "power_in"))
      (node (ref "Q1") (pin "3") (pinfunction "D_3") (pintype "bidirectional"))
      (node (ref "TP3") (pin "TP") (pinfunction "TP_TP") (pintype "input"))
      (node (ref "U4") (pin "2") (pinfunction "CELL_2") (pintype "power_in"))
      (node (ref "U4") (pin "3") (pinfunction "VDD_3") (pintype "power_in"))
    )
    (net (code "54") (name "VBUS") (class "Default")
      (node (ref "C1_BAT") (pin "1") (pinfunction "1_1") (pintype "passive"))
      (node (ref "C4_USB") (pin "1") (pinfunction "1_1") (pintype "passive"))
      (node (ref "C5_USB") (pin "1") (pinfunction "1_1") (pintype "passive"))
      (node (ref "CHG_LED") (pin "A") (pinfunction "A_A") (pintype "passive"))
      (node (ref "D1") (pin "5") (pinfunction "VBUS_5") (pintype "bidirectional"))
      (node (ref "D2") (pin "2") (pinfunction "ANODE_2") (pintype "bidirectional"))
      (node (ref "MCP73831") (pin "4") (pinfunction "VIN_4") (pintype "power_in"))
      (node (ref "PFMF.050.1") (pin "2") (pinfunction "2_2") (pintype "passive"))
      (node (ref "Q1") (pin "1") (pinfunction "G_1") (pintype "bidirectional"))
      (node (ref "R1_PWRUSB") (pin "2") (pinfunction "2_2") (pintype "passive"))
      (node (ref "TP14") (pin "TP") (pinfunction "TP_TP") (pintype "input"))
    )
    (net (code "55") (name "VRTC") (class "Default")
      (node (ref "C10_SUPERCAP") (pin "2") (pinfunction "2_2") (pintype "passive"))
      (node (ref "C8") (pin "1") (pinfunction "1_1") (pintype "passive"))
      (node (ref "R_CAPACITOR") (pin "2") (pinfunction "2_2") (pintype "passive"))
      (node (ref "U3") (pin "14") (pinfunction "VBAT_14") (pintype "power_in"))
    )
    (net (code "56") (name "VUSB") (class "Default")
      (node (ref "J2") (pin "A4") (pinfunction "A4_A4") (pintype "bidirectional"))
      (node (ref "J2") (pin "A9") (pinfunction "A9_A9") (pintype "bidirectional"))
      (node (ref "J2") (pin "B4") (pinfunction "B4_B4") (pintype "bidirectional"))
      (node (ref "J2") (pin "B9") (pinfunction "B9_B9") (pintype "bidirectional"))
      (node (ref "PFMF.050.1") (pin "1") (pinfunction "1_1") (pintype "passive"))
    )
    (net (code "57") (name "unconnected-(IC1-NC-Pad4)") (class "Default")
      (node (ref "IC1") (pin "4") (pinfunction "NC_4") (pintype "no_connect"))
    )
    (net (code "58") (name "unconnected-(IC4-NC-Pad4)") (class "Default")
      (node (ref "IC4") (pin "4") (pinfunction "NC_4") (pintype "no_connect"))
    )
    (net (code "59") (name "unconnected-(J1-Pad1)") (class "Default")
      (node (ref "J1") (pin "1") (pinfunction "1_1") (pintype "bidirectional"))
    )
    (net (code "60") (name "unconnected-(J1-Pad6)") (class "Default")
      (node (ref "J1") (pin "6") (pinfunction "6_6") (pintype "bidirectional"))
    )
    (net (code "61") (name "unconnected-(J1-Pad7)") (class "Default")
      (node (ref "J1") (pin "7") (pinfunction "7_7") (pintype "bidirectional"))
    )
    (net (code "62") (name "unconnected-(J2-PadA8)") (class "Default")
      (node (ref "J2") (pin "A8") (pinfunction "A8_A8") (pintype "bidirectional"))
    )
    (net (code "63") (name "unconnected-(J2-PadB8)") (class "Default")
      (node (ref "J2") (pin "B8") (pinfunction "B8_B8") (pintype "bidirectional"))
    )
    (net (code "64") (name "unconnected-(J4-DAT1-PadP8)") (class "Default")
      (node (ref "J4") (pin "P8") (pinfunction "DAT1_P8") (pintype "bidirectional"))
    )
    (net (code "65") (name "unconnected-(J4-DAT2-PadP1)") (class "Default")
      (node (ref "J4") (pin "P1") (pinfunction "DAT2_P1") (pintype "bidirectional"))
    )
    (net (code "66") (name "unconnected-(J4-DETECTION_1-PadS1)") (class "Default")
      (node (ref "J4") (pin "S1") (pinfunction "DETECTION_1_S1") (pintype "bidirectional"))
    )
    (net (code "67") (name "unconnected-(J4-DETECTION_2-PadS2)") (class "Default")
      (node (ref "J4") (pin "S2") (pinfunction "DETECTION_2_S2") (pintype "bidirectional"))
    )
    (net (code "68") (name "unconnected-(U2-NC-Pad22)") (class "Default")
      (node (ref "U2") (pin "22") (pinfunction "NC_22") (pintype "no_connect"))
    )
    (net (code "69") (name "unconnected-(U4-~{ALERT}-Pad5)") (class "Default")
      (node (ref "U4") (pin "5") (pinfunction "~{ALERT}_5") (pintype "output"))
    )
  )
)
